# Small_robot_PCB_schematic.net
KiCad netlist of a schematic drawn in EAGLE
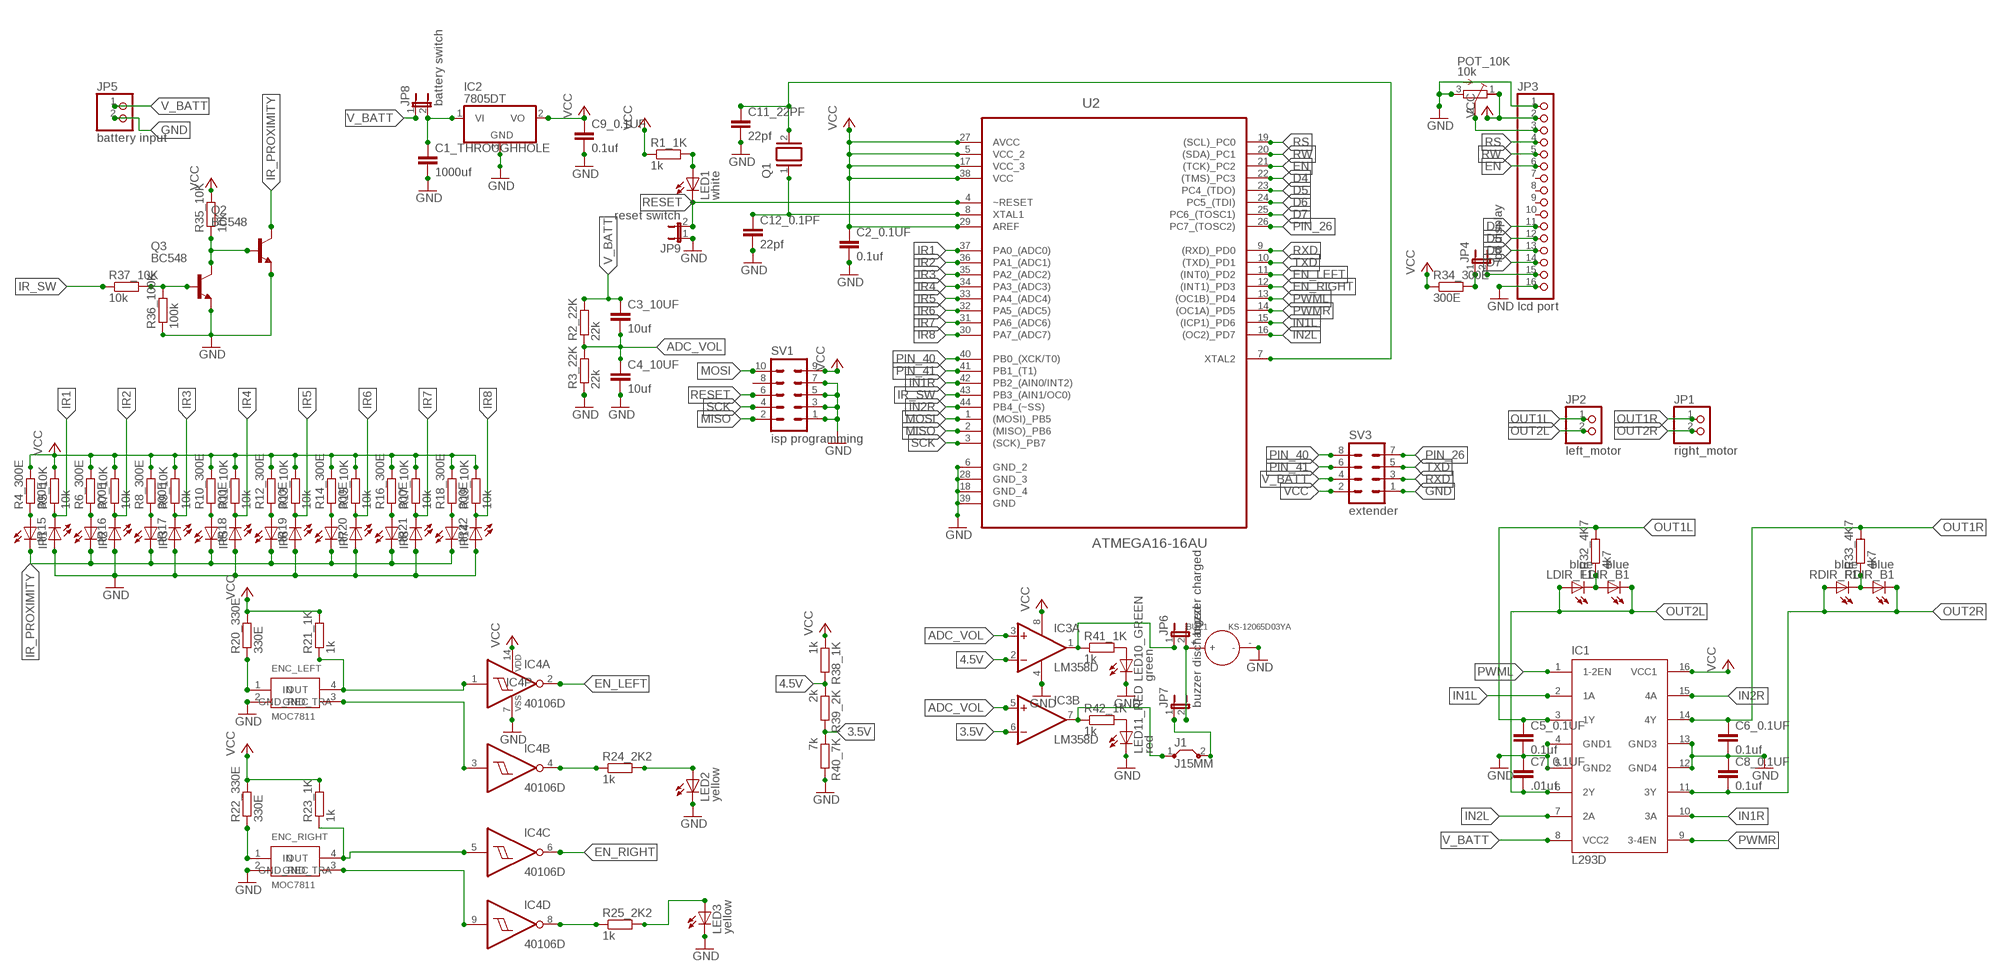
[diagram p0: schematic, sheet 1]

(export (version "E")
  (design (tool "Eeschema 10.0.6"))
  (components
    (comp (ref "BUZ1")
      (value "KS-12065D03YA")
      (footprint "eagle-import:BZ2-7.6-D12.0XH6.5MM")
      (libsource (lib "eagle-import") (part "DIP-BUZZER-3V(KS-12065D03YA)"))
    )
    (comp (ref "C1_THROUGHHOLE")
      (value "1000uf")
      (footprint "eagle-import:C050-045X075")
      (libsource (lib "eagle-import") (part "resistor_C-EU050-045X075"))
    )
    (comp (ref "C2_0.1UF")
      (value "0.1uf")
      (footprint "eagle-import:C1206")
      (libsource (lib "eagle-import") (part "resistor_C-EUC1206"))
    )
    (comp (ref "C3_10UF")
      (value "10uf")
      (footprint "eagle-import:C1206")
      (libsource (lib "eagle-import") (part "C-EUC1206"))
    )
    (comp (ref "C4_10UF")
      (value "10uf")
      (footprint "eagle-import:C1206")
      (libsource (lib "eagle-import") (part "C-EUC1206"))
    )
    (comp (ref "C5_0.1UF")
      (value "0.1uf")
      (footprint "eagle-import:C1206")
      (libsource (lib "eagle-import") (part "C-EUC1206"))
    )
    (comp (ref "C6_0.1UF")
      (value "0.1uf")
      (footprint "eagle-import:C1206")
      (libsource (lib "eagle-import") (part "C-EUC1206"))
    )
    (comp (ref "C7_0.1UF")
      (value ".01uf")
      (footprint "eagle-import:C1206")
      (libsource (lib "eagle-import") (part "C-EUC1206"))
    )
    (comp (ref "C8_0.1UF")
      (value "0.1uf")
      (footprint "eagle-import:C1206")
      (libsource (lib "eagle-import") (part "C-EUC1206"))
    )
    (comp (ref "C9_0.1UF")
      (value "0.1uf")
      (footprint "eagle-import:C1206")
      (libsource (lib "eagle-import") (part "resistor_C-EUC1206"))
    )
    (comp (ref "C11_22PF")
      (value "22pf")
      (footprint "eagle-import:C1206")
      (libsource (lib "eagle-import") (part "resistor_C-EUC1206"))
    )
    (comp (ref "C12_0.1PF")
      (value "22pf")
      (footprint "eagle-import:C1206")
      (libsource (lib "eagle-import") (part "resistor_C-EUC1206"))
    )
    (comp (ref "ENC_LEFT")
      (value "MOC7811")
      (footprint "eagle-import:THROUGH_HOLE_NORMAL")
      (libsource (lib "eagle-import") (part "MOC7811"))
    )
    (comp (ref "ENC_RIGHT")
      (value "MOC7811")
      (footprint "eagle-import:THROUGH_HOLE_NORMAL")
      (libsource (lib "eagle-import") (part "MOC7811"))
    )
    (comp (ref "IC1")
      (value "L293D")
      (footprint "eagle-import:DIL16")
      (libsource (lib "eagle-import") (part "L293D"))
    )
    (comp (ref "IC2")
      (value "7805DT")
      (footprint "eagle-import:TO252")
      (libsource (lib "eagle-import") (part "78DT05"))
    )
    (comp (ref "IC3")
      (value "LM358D")
      (footprint "eagle-import:SO08")
      (libsource (lib "eagle-import") (part "LM358D"))
    )
    (comp (ref "IC4")
      (value "40106D")
      (footprint "eagle-import:SO14")
      (libsource (lib "eagle-import") (part "40106D"))
    )
    (comp (ref "IR1")
      (value "LED5MM")
      (footprint "eagle-import:LED5MM")
      (libsource (lib "eagle-import") (part "LED5MM"))
    )
    (comp (ref "IR2")
      (value "LED5MM")
      (footprint "eagle-import:LED5MM")
      (libsource (lib "eagle-import") (part "LED5MM"))
    )
    (comp (ref "IR3")
      (value "LED5MM")
      (footprint "eagle-import:LED5MM")
      (libsource (lib "eagle-import") (part "LED5MM"))
    )
    (comp (ref "IR5")
      (value "LED5MM")
      (footprint "eagle-import:LED5MM")
      (libsource (lib "eagle-import") (part "LED5MM"))
    )
    (comp (ref "IR6")
      (value "LED5MM")
      (footprint "eagle-import:LED5MM")
      (libsource (lib "eagle-import") (part "LED5MM"))
    )
    (comp (ref "IR7")
      (value "LED5MM")
      (footprint "eagle-import:LED5MM")
      (libsource (lib "eagle-import") (part "LED5MM"))
    )
    (comp (ref "IR8")
      (value "LED5MM")
      (footprint "eagle-import:LED5MM")
      (libsource (lib "eagle-import") (part "LED5MM"))
    )
    (comp (ref "IR14")
      (value "LED5MM")
      (footprint "eagle-import:LED5MM")
      (libsource (lib "eagle-import") (part "LED5MM"))
    )
    (comp (ref "IR15")
      (value "LED5MM")
      (footprint "eagle-import:LED5MM")
      (libsource (lib "eagle-import") (part "LED5MM"))
    )
    (comp (ref "IR16")
      (value "LED5MM")
      (footprint "eagle-import:LED5MM")
      (libsource (lib "eagle-import") (part "LED5MM"))
    )
    (comp (ref "IR17")
      (value "LED5MM")
      (footprint "eagle-import:LED5MM")
      (libsource (lib "eagle-import") (part "LED5MM"))
    )
    (comp (ref "IR18")
      (value "LED5MM")
      (footprint "eagle-import:LED5MM")
      (libsource (lib "eagle-import") (part "LED5MM"))
    )
    (comp (ref "IR19")
      (value "LED5MM")
      (footprint "eagle-import:LED5MM")
      (libsource (lib "eagle-import") (part "LED5MM"))
    )
    (comp (ref "IR20")
      (value "LED5MM")
      (footprint "eagle-import:LED5MM")
      (libsource (lib "eagle-import") (part "LED5MM"))
    )
    (comp (ref "IR21")
      (value "LED5MM")
      (footprint "eagle-import:LED5MM")
      (libsource (lib "eagle-import") (part "LED5MM"))
    )
    (comp (ref "IR22")
      (value "LED5MM")
      (footprint "eagle-import:LED5MM")
      (libsource (lib "eagle-import") (part "LED5MM"))
    )
    (comp (ref "J1")
      (value "J15MM")
      (footprint "eagle-import:15")
      (libsource (lib "eagle-import") (part "J15MM"))
    )
    (comp (ref "JP1")
      (value "right_motor")
      (footprint "eagle-import:1X02")
      (libsource (lib "eagle-import") (part "PINHD-1X2"))
    )
    (comp (ref "JP2")
      (value "left_motor")
      (footprint "eagle-import:1X02")
      (libsource (lib "eagle-import") (part "PINHD-1X2"))
    )
    (comp (ref "JP3")
      (value "lcd port")
      (footprint "eagle-import:1X16")
      (libsource (lib "eagle-import") (part "PINHD-1X16"))
    )
    (comp (ref "JP4")
      (value "lcd display")
      (footprint "eagle-import:JP1")
      (libsource (lib "eagle-import") (part "JP1E"))
    )
    (comp (ref "JP5")
      (value "battery input")
      (footprint "eagle-import:1X02")
      (libsource (lib "eagle-import") (part "PINHD-1X2"))
    )
    (comp (ref "JP6")
      (value "buzzer charged")
      (footprint "eagle-import:JP1")
      (libsource (lib "eagle-import") (part "JP1E"))
    )
    (comp (ref "JP7")
      (value "buzzer discharged")
      (footprint "eagle-import:JP1")
      (libsource (lib "eagle-import") (part "JP1E"))
    )
    (comp (ref "JP8")
      (value "battery switch")
      (footprint "eagle-import:JP1")
      (libsource (lib "eagle-import") (part "JP1E"))
    )
    (comp (ref "JP9")
      (value "reset switch")
      (footprint "eagle-import:JP1")
      (libsource (lib "eagle-import") (part "JP1E"))
    )
    (comp (ref "LDIR_B1")
      (value "blue")
      (footprint "eagle-import:CHIPLED_1206")
      (libsource (lib "eagle-import") (part "LEDCHIPLED_1206"))
    )
    (comp (ref "LDIR_F1")
      (value "blue")
      (footprint "eagle-import:CHIPLED_1206")
      (libsource (lib "eagle-import") (part "LEDCHIPLED_1206"))
    )
    (comp (ref "LED1")
      (value "white")
      (footprint "eagle-import:CHIPLED_1206")
      (libsource (lib "eagle-import") (part "LEDCHIPLED_1206"))
    )
    (comp (ref "LED2")
      (value "yellow")
      (footprint "eagle-import:CHIPLED_1206")
      (libsource (lib "eagle-import") (part "LEDCHIPLED_1206"))
    )
    (comp (ref "LED3")
      (value "yellow")
      (footprint "eagle-import:CHIPLED_1206")
      (libsource (lib "eagle-import") (part "LEDCHIPLED_1206"))
    )
    (comp (ref "LED10_GREEN")
      (value "green")
      (footprint "eagle-import:CHIPLED_1206")
      (libsource (lib "eagle-import") (part "LEDCHIPLED_1206"))
    )
    (comp (ref "LED11_RED")
      (value "red")
      (footprint "eagle-import:CHIPLED_1206")
      (libsource (lib "eagle-import") (part "LEDCHIPLED_1206"))
    )
    (comp (ref "POT_10K")
      (value "10k")
      (footprint "eagle-import:RTRIMT93YA")
      (libsource (lib "eagle-import") (part "R-TRIMMT93YA"))
    )
    (comp (ref "Q1")
      (value "XTAL")
      (footprint "eagle-import:Q")
      (libsource (lib "eagle-import") (part "XTAL"))
    )
    (comp (ref "Q2")
      (value "BC548")
      (footprint "eagle-import:TO92-EBC")
      (libsource (lib "eagle-import") (part "BC548"))
    )
    (comp (ref "Q3")
      (value "BC548")
      (footprint "eagle-import:TO92-EBC")
      (libsource (lib "eagle-import") (part "BC548"))
    )
    (comp (ref "R1_1K")
      (value "1k")
      (footprint "eagle-import:R1206")
      (libsource (lib "eagle-import") (part "R-EU_R1206"))
    )
    (comp (ref "R2_22K")
      (value "22k")
      (footprint "eagle-import:R1206")
      (libsource (lib "eagle-import") (part "R-EU_R1206"))
    )
    (comp (ref "R3_22K")
      (value "22k")
      (footprint "eagle-import:R1206")
      (libsource (lib "eagle-import") (part "R-EU_R1206"))
    )
    (comp (ref "R4_300E")
      (value "300E")
      (footprint "eagle-import:R1206")
      (libsource (lib "eagle-import") (part "R-EU_R1206"))
    )
    (comp (ref "R5_10K")
      (value "10k")
      (footprint "eagle-import:R1206")
      (libsource (lib "eagle-import") (part "R-EU_R1206"))
    )
    (comp (ref "R6_300E")
      (value "300E")
      (footprint "eagle-import:R1206")
      (libsource (lib "eagle-import") (part "R-EU_R1206"))
    )
    (comp (ref "R7_10K")
      (value "10k")
      (footprint "eagle-import:R1206")
      (libsource (lib "eagle-import") (part "R-EU_R1206"))
    )
    (comp (ref "R8_300E")
      (value "300E")
      (footprint "eagle-import:R1206")
      (libsource (lib "eagle-import") (part "R-EU_R1206"))
    )
    (comp (ref "R9_10K")
      (value "10k")
      (footprint "eagle-import:R1206")
      (libsource (lib "eagle-import") (part "R-EU_R1206"))
    )
    (comp (ref "R10_300E")
      (value "300E")
      (footprint "eagle-import:R1206")
      (libsource (lib "eagle-import") (part "R-EU_R1206"))
    )
    (comp (ref "R11_10K")
      (value "10k")
      (footprint "eagle-import:R1206")
      (libsource (lib "eagle-import") (part "R-EU_R1206"))
    )
    (comp (ref "R12_300E")
      (value "300E")
      (footprint "eagle-import:R1206")
      (libsource (lib "eagle-import") (part "R-EU_R1206"))
    )
    (comp (ref "R13_10K")
      (value "10k")
      (footprint "eagle-import:R1206")
      (libsource (lib "eagle-import") (part "R-EU_R1206"))
    )
    (comp (ref "R14_300E")
      (value "300E")
      (footprint "eagle-import:R1206")
      (libsource (lib "eagle-import") (part "R-EU_R1206"))
    )
    (comp (ref "R15_10K")
      (value "10k")
      (footprint "eagle-import:R1206")
      (libsource (lib "eagle-import") (part "R-EU_R1206"))
    )
    (comp (ref "R16_300E")
      (value "300E")
      (footprint "eagle-import:R1206")
      (libsource (lib "eagle-import") (part "R-EU_R1206"))
    )
    (comp (ref "R17_10K")
      (value "10k")
      (footprint "eagle-import:R1206")
      (libsource (lib "eagle-import") (part "R-EU_R1206"))
    )
    (comp (ref "R18_300E")
      (value "300E")
      (footprint "eagle-import:R1206")
      (libsource (lib "eagle-import") (part "R-EU_R1206"))
    )
    (comp (ref "R19_10K")
      (value "10k")
      (footprint "eagle-import:R1206")
      (libsource (lib "eagle-import") (part "R-EU_R1206"))
    )
    (comp (ref "R20_330E")
      (value "330E")
      (footprint "eagle-import:R1206")
      (libsource (lib "eagle-import") (part "R-EU_R1206"))
    )
    (comp (ref "R21_1K")
      (value "1k")
      (footprint "eagle-import:R1206")
      (libsource (lib "eagle-import") (part "R-EU_R1206"))
    )
    (comp (ref "R22_330E")
      (value "330E")
      (footprint "eagle-import:R1206")
      (libsource (lib "eagle-import") (part "R-EU_R1206"))
    )
    (comp (ref "R23_1K")
      (value "1k")
      (footprint "eagle-import:R1206")
      (libsource (lib "eagle-import") (part "R-EU_R1206"))
    )
    (comp (ref "R24_2K2")
      (value "1k")
      (footprint "eagle-import:R1206")
      (libsource (lib "eagle-import") (part "R-EU_R1206"))
    )
    (comp (ref "R25_2K2")
      (value "1k")
      (footprint "eagle-import:R1206")
      (libsource (lib "eagle-import") (part "R-EU_R1206"))
    )
    (comp (ref "R32_4K7")
      (value "4k7")
      (footprint "eagle-import:R1206")
      (libsource (lib "eagle-import") (part "R-EU_R1206"))
    )
    (comp (ref "R33_4K7")
      (value "4k7")
      (footprint "eagle-import:R1206")
      (libsource (lib "eagle-import") (part "R-EU_R1206"))
    )
    (comp (ref "R34_300E")
      (value "300E")
      (footprint "eagle-import:R1206")
      (libsource (lib "eagle-import") (part "R-EU_R1206"))
    )
    (comp (ref "R35_10K")
      (value "10k")
      (footprint "eagle-import:R1206")
      (libsource (lib "eagle-import") (part "R-EU_R1206"))
    )
    (comp (ref "R36_100K")
      (value "100k")
      (footprint "eagle-import:R1206")
      (libsource (lib "eagle-import") (part "R-EU_R1206"))
    )
    (comp (ref "R37_10K")
      (value "10k")
      (footprint "eagle-import:R1206")
      (libsource (lib "eagle-import") (part "R-EU_R1206"))
    )
    (comp (ref "R38_1K")
      (value "1k")
      (footprint "eagle-import:R1206")
      (libsource (lib "eagle-import") (part "R-EU_R1206"))
    )
    (comp (ref "R39_2K")
      (value "2k")
      (footprint "eagle-import:R1206")
      (libsource (lib "eagle-import") (part "R-EU_R1206"))
    )
    (comp (ref "R40_7K")
      (value "7k")
      (footprint "eagle-import:R1206")
      (libsource (lib "eagle-import") (part "R-EU_R1206"))
    )
    (comp (ref "R41_1K")
      (value "1k")
      (footprint "eagle-import:R1206")
      (libsource (lib "eagle-import") (part "R-EU_R1206"))
    )
    (comp (ref "R42_1K")
      (value "1k")
      (footprint "eagle-import:R1206")
      (libsource (lib "eagle-import") (part "R-EU_R1206"))
    )
    (comp (ref "RDIR_B1")
      (value "blue")
      (footprint "eagle-import:CHIPLED_1206")
      (libsource (lib "eagle-import") (part "LEDCHIPLED_1206"))
    )
    (comp (ref "RDIR_F1")
      (value "blue")
      (footprint "eagle-import:CHIPLED_1206")
      (libsource (lib "eagle-import") (part "LEDCHIPLED_1206"))
    )
    (comp (ref "SV1")
      (value "isp programming")
      (footprint "eagle-import:MA05-2")
      (libsource (lib "eagle-import") (part "MA05-2"))
    )
    (comp (ref "SV3")
      (value "extender")
      (footprint "eagle-import:MA04-2")
      (libsource (lib "eagle-import") (part "MA04-2"))
    )
    (comp (ref "U2")
      (value "ATMEGA16-16AU")
      (footprint "eagle-import:QFP80P1200X1200X120-44N")
      (libsource (lib "eagle-import") (part "ATMEGA16-16AU"))
    )
  )
  (nets
    (net (code "1") (name "3.5V") (class "Default")
      (node (ref "IC3") (pin "6") (pinfunction "-IN_6") (pintype "input"))
      (node (ref "R39_2K") (pin "2") (pinfunction "2_2") (pintype "passive"))
      (node (ref "R40_7K") (pin "1") (pinfunction "1_1") (pintype "passive"))
    )
    (net (code "2") (name "4.5V") (class "Default")
      (node (ref "IC3") (pin "2") (pinfunction "-IN_2") (pintype "input"))
      (node (ref "R38_1K") (pin "2") (pinfunction "2_2") (pintype "passive"))
      (node (ref "R39_2K") (pin "1") (pinfunction "1_1") (pintype "passive"))
    )
    (net (code "3") (name "ADC_VOL") (class "Default")
      (node (ref "C3_10UF") (pin "2") (pinfunction "2_2") (pintype "passive"))
      (node (ref "C4_10UF") (pin "1") (pinfunction "1_1") (pintype "passive"))
      (node (ref "IC3") (pin "3") (pinfunction "+IN_3") (pintype "input"))
      (node (ref "IC3") (pin "5") (pinfunction "+IN_5") (pintype "input"))
      (node (ref "R2_22K") (pin "1") (pinfunction "1_1") (pintype "passive"))
      (node (ref "R3_22K") (pin "2") (pinfunction "2_2") (pintype "passive"))
    )
    (net (code "4") (name "D4") (class "Default")
      (node (ref "JP3") (pin "11") (pinfunction "11_11") (pintype "passive"))
      (node (ref "U2") (pin "22") (pinfunction "(TMS)_PC3_22") (pintype "bidirectional"))
    )
    (net (code "5") (name "D5") (class "Default")
      (node (ref "JP3") (pin "12") (pinfunction "12_12") (pintype "passive"))
      (node (ref "U2") (pin "23") (pinfunction "PC4_(TDO)_23") (pintype "bidirectional"))
    )
    (net (code "6") (name "D6") (class "Default")
      (node (ref "JP3") (pin "13") (pinfunction "13_13") (pintype "passive"))
      (node (ref "U2") (pin "24") (pinfunction "PC5_(TDI)_24") (pintype "bidirectional"))
    )
    (net (code "7") (name "D7") (class "Default")
      (node (ref "JP3") (pin "14") (pinfunction "14_14") (pintype "passive"))
      (node (ref "U2") (pin "25") (pinfunction "PC6_(TOSC1)_25") (pintype "bidirectional"))
    )
    (net (code "8") (name "EN") (class "Default")
      (node (ref "JP3") (pin "6") (pinfunction "6_6") (pintype "passive"))
      (node (ref "U2") (pin "21") (pinfunction "(TCK)_PC2_21") (pintype "bidirectional"))
    )
    (net (code "9") (name "EN_LEFT") (class "Default")
      (node (ref "IC4") (pin "2") (pinfunction "O_2") (pintype "output"))
      (node (ref "U2") (pin "11") (pinfunction "(INT0)_PD2_11") (pintype "bidirectional"))
    )
    (net (code "10") (name "EN_RIGHT") (class "Default")
      (node (ref "IC4") (pin "6") (pinfunction "O_6") (pintype "output"))
      (node (ref "U2") (pin "12") (pinfunction "(INT1)_PD3_12") (pintype "bidirectional"))
    )
    (net (code "11") (name "GND") (class "Default")
      (node (ref "BUZ1") (pin "-") (pinfunction "-_-") (pintype "bidirectional"))
      (node (ref "C11_22PF") (pin "2") (pinfunction "2_2") (pintype "passive"))
      (node (ref "C12_0.1PF") (pin "2") (pinfunction "2_2") (pintype "passive"))
      (node (ref "C1_THROUGHHOLE") (pin "2") (pinfunction "2_2") (pintype "passive"))
      (node (ref "C2_0.1UF") (pin "2") (pinfunction "2_2") (pintype "passive"))
      (node (ref "C4_10UF") (pin "2") (pinfunction "2_2") (pintype "passive"))
      (node (ref "C5_0.1UF") (pin "2") (pinfunction "2_2") (pintype "passive"))
      (node (ref "C6_0.1UF") (pin "2") (pinfunction "2_2") (pintype "passive"))
      (node (ref "C7_0.1UF") (pin "1") (pinfunction "1_1") (pintype "passive"))
      (node (ref "C8_0.1UF") (pin "1") (pinfunction "1_1") (pintype "passive"))
      (node (ref "C9_0.1UF") (pin "2") (pinfunction "2_2") (pintype "passive"))
      (node (ref "ENC_LEFT") (pin "2") (pinfunction "GND_TRA_2") (pintype "bidirectional"))
      (node (ref "ENC_RIGHT") (pin "2") (pinfunction "GND_TRA_2") (pintype "bidirectional"))
      (node (ref "IC1") (pin "12") (pinfunction "GND4_12") (pintype "power_in"))
      (node (ref "IC1") (pin "13") (pinfunction "GND3_13") (pintype "power_in"))
      (node (ref "IC1") (pin "4") (pinfunction "GND1_4") (pintype "power_in"))
      (node (ref "IC1") (pin "5") (pinfunction "GND2_5") (pintype "power_in"))
      (node (ref "IC2") (pin "3") (pinfunction "GND_3") (pintype "passive"))
      (node (ref "IC3") (pin "4") (pinfunction "V-_4") (pintype "power_in"))
      (node (ref "IC4") (pin "7") (pinfunction "VSS_7") (pintype "power_in"))
      (node (ref "IR15") (pin "A") (pinfunction "A_A") (pintype "passive"))
      (node (ref "IR16") (pin "A") (pinfunction "A_A") (pintype "passive"))
      (node (ref "IR17") (pin "A") (pinfunction "A_A") (pintype "passive"))
      (node (ref "IR18") (pin "A") (pinfunction "A_A") (pintype "passive"))
      (node (ref "IR19") (pin "A") (pinfunction "A_A") (pintype "passive"))
      (node (ref "IR20") (pin "A") (pinfunction "A_A") (pintype "passive"))
      (node (ref "IR21") (pin "A") (pinfunction "A_A") (pintype "passive"))
      (node (ref "IR22") (pin "A") (pinfunction "A_A") (pintype "passive"))
      (node (ref "JP3") (pin "1") (pinfunction "1_1") (pintype "passive"))
      (node (ref "JP3") (pin "16") (pinfunction "16_16") (pintype "passive"))
      (node (ref "JP5") (pin "2") (pinfunction "2_2") (pintype "passive"))
      (node (ref "JP9") (pin "1") (pinfunction "1_1") (pintype "passive"))
      (node (ref "LED10_GREEN") (pin "C") (pinfunction "C_C") (pintype "passive"))
      (node (ref "LED11_RED") (pin "C") (pinfunction "C_C") (pintype "passive"))
      (node (ref "LED2") (pin "C") (pinfunction "C_C") (pintype "passive"))
      (node (ref "LED3") (pin "C") (pinfunction "C_C") (pintype "passive"))
      (node (ref "POT_10K") (pin "3") (pinfunction "A_3") (pintype "passive"))
      (node (ref "Q2") (pin "E") (pinfunction "E_E") (pintype "passive"))
      (node (ref "Q3") (pin "E") (pinfunction "E_E") (pintype "passive"))
      (node (ref "R36_100K") (pin "1") (pinfunction "1_1") (pintype "passive"))
      (node (ref "R3_22K") (pin "1") (pinfunction "1_1") (pintype "passive"))
      (node (ref "R40_7K") (pin "2") (pinfunction "2_2") (pintype "passive"))
      (node (ref "SV1") (pin "1") (pinfunction "1_1") (pintype "passive"))
      (node (ref "SV1") (pin "3") (pinfunction "3_3") (pintype "passive"))
      (node (ref "SV1") (pin "5") (pinfunction "5_5") (pintype "passive"))
      (node (ref "SV1") (pin "7") (pinfunction "7_7") (pintype "passive"))
      (node (ref "SV3") (pin "1") (pinfunction "1_1") (pintype "passive"))
      (node (ref "U2") (pin "18") (pinfunction "GND_4_18") (pintype "passive"))
      (node (ref "U2") (pin "28") (pinfunction "GND_3_28") (pintype "passive"))
      (node (ref "U2") (pin "39") (pinfunction "GND_39") (pintype "passive"))
      (node (ref "U2") (pin "6") (pinfunction "GND_2_6") (pintype "passive"))
    )
    (net (code "12") (name "IN1L") (class "Default")
      (node (ref "IC1") (pin "2") (pinfunction "1A_2") (pintype "input"))
      (node (ref "U2") (pin "15") (pinfunction "(ICP1)_PD6_15") (pintype "bidirectional"))
    )
    (net (code "13") (name "IN1R") (class "Default")
      (node (ref "IC1") (pin "10") (pinfunction "3A_10") (pintype "input"))
      (node (ref "U2") (pin "42") (pinfunction "PB2_(AIN0/INT2)_42") (pintype "bidirectional"))
    )
    (net (code "14") (name "IN2L") (class "Default")
      (node (ref "IC1") (pin "7") (pinfunction "2A_7") (pintype "input"))
      (node (ref "U2") (pin "16") (pinfunction "(OC2)_PD7_16") (pintype "bidirectional"))
    )
    (net (code "15") (name "IN2R") (class "Default")
      (node (ref "IC1") (pin "15") (pinfunction "4A_15") (pintype "input"))
      (node (ref "U2") (pin "44") (pinfunction "PB4_(~{SS})_44") (pintype "bidirectional"))
    )
    (net (code "16") (name "IR1") (class "Default")
      (node (ref "IR15") (pin "K") (pinfunction "C_K") (pintype "passive"))
      (node (ref "R5_10K") (pin "1") (pinfunction "1_1") (pintype "passive"))
      (node (ref "U2") (pin "37") (pinfunction "PA0_(ADC0)_37") (pintype "bidirectional"))
    )
    (net (code "17") (name "IR2") (class "Default")
      (node (ref "IR16") (pin "K") (pinfunction "C_K") (pintype "passive"))
      (node (ref "R7_10K") (pin "1") (pinfunction "1_1") (pintype "passive"))
      (node (ref "U2") (pin "36") (pinfunction "PA1_(ADC1)_36") (pintype "bidirectional"))
    )
    (net (code "18") (name "IR3") (class "Default")
      (node (ref "IR17") (pin "K") (pinfunction "C_K") (pintype "passive"))
      (node (ref "R9_10K") (pin "1") (pinfunction "1_1") (pintype "passive"))
      (node (ref "U2") (pin "35") (pinfunction "PA2_(ADC2)_35") (pintype "bidirectional"))
    )
    (net (code "19") (name "IR4") (class "Default")
      (node (ref "IR18") (pin "K") (pinfunction "C_K") (pintype "passive"))
      (node (ref "R11_10K") (pin "1") (pinfunction "1_1") (pintype "passive"))
      (node (ref "U2") (pin "34") (pinfunction "PA3_(ADC3)_34") (pintype "bidirectional"))
    )
    (net (code "20") (name "IR5") (class "Default")
      (node (ref "IR19") (pin "K") (pinfunction "C_K") (pintype "passive"))
      (node (ref "R13_10K") (pin "1") (pinfunction "1_1") (pintype "passive"))
      (node (ref "U2") (pin "33") (pinfunction "PA4_(ADC4)_33") (pintype "bidirectional"))
    )
    (net (code "21") (name "IR6") (class "Default")
      (node (ref "IR20") (pin "K") (pinfunction "C_K") (pintype "passive"))
      (node (ref "R15_10K") (pin "1") (pinfunction "1_1") (pintype "passive"))
      (node (ref "U2") (pin "32") (pinfunction "PA5_(ADC5)_32") (pintype "bidirectional"))
    )
    (net (code "22") (name "IR7") (class "Default")
      (node (ref "IR21") (pin "K") (pinfunction "C_K") (pintype "passive"))
      (node (ref "R17_10K") (pin "1") (pinfunction "1_1") (pintype "passive"))
      (node (ref "U2") (pin "31") (pinfunction "PA6_(ADC6)_31") (pintype "bidirectional"))
    )
    (net (code "23") (name "IR8") (class "Default")
      (node (ref "IR22") (pin "K") (pinfunction "C_K") (pintype "passive"))
      (node (ref "R19_10K") (pin "1") (pinfunction "1_1") (pintype "passive"))
      (node (ref "U2") (pin "30") (pinfunction "PA7_(ADC7)_30") (pintype "bidirectional"))
    )
    (net (code "24") (name "IR_PROXIMITY") (class "Default")
      (node (ref "IR1") (pin "K") (pinfunction "C_K") (pintype "passive"))
      (node (ref "IR14") (pin "K") (pinfunction "C_K") (pintype "passive"))
      (node (ref "IR2") (pin "K") (pinfunction "C_K") (pintype "passive"))
      (node (ref "IR3") (pin "K") (pinfunction "C_K") (pintype "passive"))
      (node (ref "IR5") (pin "K") (pinfunction "C_K") (pintype "passive"))
      (node (ref "IR6") (pin "K") (pinfunction "C_K") (pintype "passive"))
      (node (ref "IR7") (pin "K") (pinfunction "C_K") (pintype "passive"))
      (node (ref "IR8") (pin "K") (pinfunction "C_K") (pintype "passive"))
      (node (ref "Q2") (pin "C") (pinfunction "C_C") (pintype "passive"))
    )
    (net (code "25") (name "IR_SW") (class "Default")
      (node (ref "R37_10K") (pin "1") (pinfunction "1_1") (pintype "passive"))
      (node (ref "U2") (pin "43") (pinfunction "PB3_(AIN1/OC0)_43") (pintype "bidirectional"))
    )
    (net (code "26") (name "MISO") (class "Default")
      (node (ref "SV1") (pin "2") (pinfunction "2_2") (pintype "passive"))
      (node (ref "U2") (pin "2") (pinfunction "(MISO)_PB6_2") (pintype "bidirectional"))
    )
    (net (code "27") (name "MOSI") (class "Default")
      (node (ref "SV1") (pin "10") (pinfunction "10_10") (pintype "passive"))
      (node (ref "U2") (pin "1") (pinfunction "(MOSI)_PB5_1") (pintype "bidirectional"))
    )
    (net (code "28") (name "Net-(BUZ1-Pad+)") (class "Default")
      (node (ref "BUZ1") (pin "+") (pinfunction "+_+") (pintype "bidirectional"))
      (node (ref "JP6") (pin "2") (pinfunction "2_2") (pintype "passive"))
      (node (ref "JP7") (pin "2") (pinfunction "2_2") (pintype "passive"))
    )
    (net (code "29") (name "Net-(ENC_LEFT-GND_REC)") (class "Default")
      (node (ref "ENC_LEFT") (pin "3") (pinfunction "GND_REC_3") (pintype "bidirectional"))
      (node (ref "IC4") (pin "3") (pinfunction "I_3") (pintype "input"))
    )
    (net (code "30") (name "Net-(ENC_LEFT-IN)") (class "Default")
      (node (ref "ENC_LEFT") (pin "1") (pinfunction "IN_1") (pintype "bidirectional"))
      (node (ref "R20_330E") (pin "1") (pinfunction "1_1") (pintype "passive"))
    )
    (net (code "31") (name "Net-(ENC_LEFT-OUT)") (class "Default")
      (node (ref "ENC_LEFT") (pin "4") (pinfunction "OUT_4") (pintype "bidirectional"))
      (node (ref "IC4") (pin "1") (pinfunction "I_1") (pintype "input"))
      (node (ref "R21_1K") (pin "1") (pinfunction "1_1") (pintype "passive"))
    )
    (net (code "32") (name "Net-(ENC_RIGHT-GND_REC)") (class "Default")
      (node (ref "ENC_RIGHT") (pin "3") (pinfunction "GND_REC_3") (pintype "bidirectional"))
      (node (ref "IC4") (pin "9") (pinfunction "I_9") (pintype "input"))
    )
    (net (code "33") (name "Net-(ENC_RIGHT-IN)") (class "Default")
      (node (ref "ENC_RIGHT") (pin "1") (pinfunction "IN_1") (pintype "bidirectional"))
      (node (ref "R22_330E") (pin "1") (pinfunction "1_1") (pintype "passive"))
    )
    (net (code "34") (name "Net-(ENC_RIGHT-OUT)") (class "Default")
      (node (ref "ENC_RIGHT") (pin "4") (pinfunction "OUT_4") (pintype "bidirectional"))
      (node (ref "IC4") (pin "5") (pinfunction "I_5") (pintype "input"))
      (node (ref "R23_1K") (pin "1") (pinfunction "1_1") (pintype "passive"))
    )
    (net (code "35") (name "Net-(IC2-VI)") (class "Default")
      (node (ref "C1_THROUGHHOLE") (pin "1") (pinfunction "1_1") (pintype "passive"))
      (node (ref "IC2") (pin "1") (pinfunction "VI_1") (pintype "input"))
      (node (ref "JP8") (pin "2") (pinfunction "2_2") (pintype "passive"))
    )
    (net (code "36") (name "Net-(IC3A-OUT)") (class "Default")
      (node (ref "IC3") (pin "1") (pinfunction "OUT_1") (pintype "output"))
      (node (ref "JP6") (pin "1") (pinfunction "1_1") (pintype "passive"))
      (node (ref "R41_1K") (pin "1") (pinfunction "1_1") (pintype "passive"))
    )
    (net (code "37") (name "Net-(IC3B-OUT)") (class "Default")
      (node (ref "IC3") (pin "7") (pinfunction "OUT_7") (pintype "output"))
      (node (ref "J1") (pin "1") (pinfunction "1_1") (pintype "passive"))
      (node (ref "R42_1K") (pin "1") (pinfunction "1_1") (pintype "passive"))
    )
    (net (code "38") (name "Net-(IC4B-O)") (class "Default")
      (node (ref "IC4") (pin "4") (pinfunction "O_4") (pintype "output"))
      (node (ref "R24_2K2") (pin "1") (pinfunction "1_1") (pintype "passive"))
    )
    (net (code "39") (name "Net-(IC4D-O)") (class "Default")
      (node (ref "IC4") (pin "8") (pinfunction "O_8") (pintype "output"))
      (node (ref "R25_2K2") (pin "1") (pinfunction "1_1") (pintype "passive"))
    )
    (net (code "40") (name "Net-(IR1-PadA)") (class "Default")
      (node (ref "IR1") (pin "A") (pinfunction "A_A") (pintype "passive"))
      (node (ref "R4_300E") (pin "1") (pinfunction "1_1") (pintype "passive"))
    )
    (net (code "41") (name "Net-(IR2-PadA)") (class "Default")
      (node (ref "IR2") (pin "A") (pinfunction "A_A") (pintype "passive"))
      (node (ref "R6_300E") (pin "1") (pinfunction "1_1") (pintype "passive"))
    )
    (net (code "42") (name "Net-(IR3-PadA)") (class "Default")
      (node (ref "IR3") (pin "A") (pinfunction "A_A") (pintype "passive"))
      (node (ref "R8_300E") (pin "1") (pinfunction "1_1") (pintype "passive"))
    )
    (net (code "43") (name "Net-(IR5-PadA)") (class "Default")
      (node (ref "IR5") (pin "A") (pinfunction "A_A") (pintype "passive"))
      (node (ref "R10_300E") (pin "1") (pinfunction "1_1") (pintype "passive"))
    )
    (net (code "44") (name "Net-(IR6-PadA)") (class "Default")
      (node (ref "IR6") (pin "A") (pinfunction "A_A") (pintype "passive"))
      (node (ref "R12_300E") (pin "1") (pinfunction "1_1") (pintype "passive"))
    )
    (net (code "45") (name "Net-(IR7-PadA)") (class "Default")
      (node (ref "IR7") (pin "A") (pinfunction "A_A") (pintype "passive"))
      (node (ref "R14_300E") (pin "1") (pinfunction "1_1") (pintype "passive"))
    )
    (net (code "46") (name "Net-(IR8-PadA)") (class "Default")
      (node (ref "IR8") (pin "A") (pinfunction "A_A") (pintype "passive"))
      (node (ref "R16_300E") (pin "1") (pinfunction "1_1") (pintype "passive"))
    )
    (net (code "47") (name "Net-(IR14-PadA)") (class "Default")
      (node (ref "IR14") (pin "A") (pinfunction "A_A") (pintype "passive"))
      (node (ref "R18_300E") (pin "1") (pinfunction "1_1") (pintype "passive"))
    )
    (net (code "48") (name "Net-(J1-Pad2)") (class "Default")
      (node (ref "J1") (pin "2") (pinfunction "2_2") (pintype "passive"))
      (node (ref "JP7") (pin "1") (pinfunction "1_1") (pintype "passive"))
    )
    (net (code "49") (name "Net-(JP3-Pad15)") (class "Default")
      (node (ref "JP3") (pin "15") (pinfunction "15_15") (pintype "passive"))
      (node (ref "JP4") (pin "2") (pinfunction "2_2") (pintype "passive"))
    )
    (net (code "50") (name "Net-(JP4-Pad1)") (class "Default")
      (node (ref "JP4") (pin "1") (pinfunction "1_1") (pintype "passive"))
      (node (ref "R34_300E") (pin "2") (pinfunction "2_2") (pintype "passive"))
    )
    (net (code "51") (name "Net-(LDIR_B1-PadA)") (class "Default")
      (node (ref "LDIR_B1") (pin "A") (pinfunction "A_A") (pintype "passive"))
      (node (ref "LDIR_F1") (pin "C") (pinfunction "C_C") (pintype "passive"))
      (node (ref "R32_4K7") (pin "1") (pinfunction "1_1") (pintype "passive"))
    )
    (net (code "52") (name "Net-(LED1-PadA)") (class "Default")
      (node (ref "LED1") (pin "A") (pinfunction "A_A") (pintype "passive"))
      (node (ref "R1_1K") (pin "2") (pinfunction "2_2") (pintype "passive"))
    )
    (net (code "53") (name "Net-(LED2-PadA)") (class "Default")
      (node (ref "LED2") (pin "A") (pinfunction "A_A") (pintype "passive"))
      (node (ref "R24_2K2") (pin "2") (pinfunction "2_2") (pintype "passive"))
    )
    (net (code "54") (name "Net-(LED3-PadA)") (class "Default")
      (node (ref "LED3") (pin "A") (pinfunction "A_A") (pintype "passive"))
      (node (ref "R25_2K2") (pin "2") (pinfunction "2_2") (pintype "passive"))
    )
    (net (code "55") (name "Net-(LED10_GREEN-PadA)") (class "Default")
      (node (ref "LED10_GREEN") (pin "A") (pinfunction "A_A") (pintype "passive"))
      (node (ref "R41_1K") (pin "2") (pinfunction "2_2") (pintype "passive"))
    )
    (net (code "56") (name "Net-(LED11_RED-PadA)") (class "Default")
      (node (ref "LED11_RED") (pin "A") (pinfunction "A_A") (pintype "passive"))
      (node (ref "R42_1K") (pin "2") (pinfunction "2_2") (pintype "passive"))
    )
    (net (code "57") (name "Net-(POT_10K-S)") (class "Default")
      (node (ref "JP3") (pin "3") (pinfunction "3_3") (pintype "passive"))
      (node (ref "POT_10K") (pin "2") (pinfunction "S_2") (pintype "passive"))
    )
    (net (code "58") (name "Net-(Q2-PadB)") (class "Default")
      (node (ref "Q2") (pin "B") (pinfunction "B_B") (pintype "passive"))
      (node (ref "Q3") (pin "C") (pinfunction "C_C") (pintype "passive"))
      (node (ref "R35_10K") (pin "1") (pinfunction "1_1") (pintype "passive"))
    )
    (net (code "59") (name "Net-(Q3-PadB)") (class "Default")
      (node (ref "Q3") (pin "B") (pinfunction "B_B") (pintype "passive"))
      (node (ref "R36_100K") (pin "2") (pinfunction "2_2") (pintype "passive"))
      (node (ref "R37_10K") (pin "2") (pinfunction "2_2") (pintype "passive"))
    )
    (net (code "60") (name "Net-(R33_4K7-Pad1)") (class "Default")
      (node (ref "R33_4K7") (pin "1") (pinfunction "1_1") (pintype "passive"))
      (node (ref "RDIR_B1") (pin "A") (pinfunction "A_A") (pintype "passive"))
      (node (ref "RDIR_F1") (pin "C") (pinfunction "C_C") (pintype "passive"))
    )
    (net (code "61") (name "Net-(U2-XTAL1)") (class "Default")
      (node (ref "C12_0.1PF") (pin "1") (pinfunction "1_1") (pintype "passive"))
      (node (ref "Q1") (pin "1") (pinfunction "1_1") (pintype "passive"))
      (node (ref "U2") (pin "8") (pinfunction "XTAL1_8") (pintype "input"))
    )
    (net (code "62") (name "Net-(U2-XTAL2)") (class "Default")
      (node (ref "C11_22PF") (pin "1") (pinfunction "1_1") (pintype "passive"))
      (node (ref "Q1") (pin "2") (pinfunction "2_2") (pintype "passive"))
      (node (ref "U2") (pin "7") (pinfunction "XTAL2_7") (pintype "output"))
    )
    (net (code "63") (name "OUT1L") (class "Default")
      (node (ref "C5_0.1UF") (pin "1") (pinfunction "1_1") (pintype "passive"))
      (node (ref "IC1") (pin "3") (pinfunction "1Y_3") (pintype "output"))
      (node (ref "JP2") (pin "1") (pinfunction "1_1") (pintype "passive"))
      (node (ref "R32_4K7") (pin "2") (pinfunction "2_2") (pintype "passive"))
    )
    (net (code "64") (name "OUT1R") (class "Default")
      (node (ref "C6_0.1UF") (pin "1") (pinfunction "1_1") (pintype "passive"))
      (node (ref "IC1") (pin "14") (pinfunction "4Y_14") (pintype "output"))
      (node (ref "JP1") (pin "1") (pinfunction "1_1") (pintype "passive"))
      (node (ref "R33_4K7") (pin "2") (pinfunction "2_2") (pintype "passive"))
    )
    (net (code "65") (name "OUT2L") (class "Default")
      (node (ref "C7_0.1UF") (pin "2") (pinfunction "2_2") (pintype "passive"))
      (node (ref "IC1") (pin "6") (pinfunction "2Y_6") (pintype "output"))
      (node (ref "JP2") (pin "2") (pinfunction "2_2") (pintype "passive"))
      (node (ref "LDIR_B1") (pin "C") (pinfunction "C_C") (pintype "passive"))
      (node (ref "LDIR_F1") (pin "A") (pinfunction "A_A") (pintype "passive"))
    )
    (net (code "66") (name "OUT2R") (class "Default")
      (node (ref "C8_0.1UF") (pin "2") (pinfunction "2_2") (pintype "passive"))
      (node (ref "IC1") (pin "11") (pinfunction "3Y_11") (pintype "output"))
      (node (ref "JP1") (pin "2") (pinfunction "2_2") (pintype "passive"))
      (node (ref "RDIR_B1") (pin "C") (pinfunction "C_C") (pintype "passive"))
      (node (ref "RDIR_F1") (pin "A") (pinfunction "A_A") (pintype "passive"))
    )
    (net (code "67") (name "PIN_26") (class "Default")
      (node (ref "SV3") (pin "7") (pinfunction "7_7") (pintype "passive"))
      (node (ref "U2") (pin "26") (pinfunction "PC7_(TOSC2)_26") (pintype "bidirectional"))
    )
    (net (code "68") (name "PIN_40") (class "Default")
      (node (ref "SV3") (pin "8") (pinfunction "8_8") (pintype "passive"))
      (node (ref "U2") (pin "40") (pinfunction "PB0_(XCK/T0)_40") (pintype "bidirectional"))
    )
    (net (code "69") (name "PIN_41") (class "Default")
      (node (ref "SV3") (pin "6") (pinfunction "6_6") (pintype "passive"))
      (node (ref "U2") (pin "41") (pinfunction "PB1_(T1)_41") (pintype "bidirectional"))
    )
    (net (code "70") (name "PWML") (class "Default")
      (node (ref "IC1") (pin "1") (pinfunction "1-2EN_1") (pintype "input"))
      (node (ref "U2") (pin "13") (pinfunction "(OC1B)_PD4_13") (pintype "bidirectional"))
    )
    (net (code "71") (name "PWMR") (class "Default")
      (node (ref "IC1") (pin "9") (pinfunction "3-4EN_9") (pintype "input"))
      (node (ref "U2") (pin "14") (pinfunction "(OC1A)_PD5_14") (pintype "bidirectional"))
    )
    (net (code "72") (name "RESET") (class "Default")
      (node (ref "JP9") (pin "2") (pinfunction "2_2") (pintype "passive"))
      (node (ref "LED1") (pin "C") (pinfunction "C_C") (pintype "passive"))
      (node (ref "SV1") (pin "6") (pinfunction "6_6") (pintype "passive"))
      (node (ref "U2") (pin "4") (pinfunction "~{RESET}_4") (pintype "input"))
    )
    (net (code "73") (name "RS") (class "Default")
      (node (ref "JP3") (pin "4") (pinfunction "4_4") (pintype "passive"))
      (node (ref "U2") (pin "19") (pinfunction "(SCL)_PC0_19") (pintype "bidirectional"))
    )
    (net (code "74") (name "RW") (class "Default")
      (node (ref "JP3") (pin "5") (pinfunction "5_5") (pintype "passive"))
      (node (ref "U2") (pin "20") (pinfunction "(SDA)_PC1_20") (pintype "bidirectional"))
    )
    (net (code "75") (name "RXD") (class "Default")
      (node (ref "SV3") (pin "3") (pinfunction "3_3") (pintype "passive"))
      (node (ref "U2") (pin "9") (pinfunction "(RXD)_PD0_9") (pintype "bidirectional"))
    )
    (net (code "76") (name "SCK") (class "Default")
      (node (ref "SV1") (pin "4") (pinfunction "4_4") (pintype "passive"))
      (node (ref "U2") (pin "3") (pinfunction "(SCK)_PB7_3") (pintype "bidirectional"))
    )
    (net (code "77") (name "TXD") (class "Default")
      (node (ref "SV3") (pin "5") (pinfunction "5_5") (pintype "passive"))
      (node (ref "U2") (pin "10") (pinfunction "(TXD)_PD1_10") (pintype "bidirectional"))
    )
    (net (code "78") (name "VCC") (class "Default")
      (node (ref "C2_0.1UF") (pin "1") (pinfunction "1_1") (pintype "passive"))
      (node (ref "C9_0.1UF") (pin "1") (pinfunction "1_1") (pintype "passive"))
      (node (ref "IC1") (pin "16") (pinfunction "VCC1_16") (pintype "power_in"))
      (node (ref "IC2") (pin "2") (pinfunction "VO_2") (pintype "passive"))
      (node (ref "IC3") (pin "8") (pinfunction "V+_8") (pintype "power_in"))
      (node (ref "IC4") (pin "14") (pinfunction "VDD_14") (pintype "power_in"))
      (node (ref "JP3") (pin "2") (pinfunction "2_2") (pintype "passive"))
      (node (ref "POT_10K") (pin "1") (pinfunction "E_1") (pintype "passive"))
      (node (ref "R10_300E") (pin "2") (pinfunction "2_2") (pintype "passive"))
      (node (ref "R11_10K") (pin "2") (pinfunction "2_2") (pintype "passive"))
      (node (ref "R12_300E") (pin "2") (pinfunction "2_2") (pintype "passive"))
      (node (ref "R13_10K") (pin "2") (pinfunction "2_2") (pintype "passive"))
      (node (ref "R14_300E") (pin "2") (pinfunction "2_2") (pintype "passive"))
      (node (ref "R15_10K") (pin "2") (pinfunction "2_2") (pintype "passive"))
      (node (ref "R16_300E") (pin "2") (pinfunction "2_2") (pintype "passive"))
      (node (ref "R17_10K") (pin "2") (pinfunction "2_2") (pintype "passive"))
      (node (ref "R18_300E") (pin "2") (pinfunction "2_2") (pintype "passive"))
      (node (ref "R19_10K") (pin "2") (pinfunction "2_2") (pintype "passive"))
      (node (ref "R1_1K") (pin "1") (pinfunction "1_1") (pintype "passive"))
      (node (ref "R20_330E") (pin "2") (pinfunction "2_2") (pintype "passive"))
      (node (ref "R21_1K") (pin "2") (pinfunction "2_2") (pintype "passive"))
      (node (ref "R22_330E") (pin "2") (pinfunction "2_2") (pintype "passive"))
      (node (ref "R23_1K") (pin "2") (pinfunction "2_2") (pintype "passive"))
      (node (ref "R34_300E") (pin "1") (pinfunction "1_1") (pintype "passive"))
      (node (ref "R35_10K") (pin "2") (pinfunction "2_2") (pintype "passive"))
      (node (ref "R38_1K") (pin "1") (pinfunction "1_1") (pintype "passive"))
      (node (ref "R4_300E") (pin "2") (pinfunction "2_2") (pintype "passive"))
      (node (ref "R5_10K") (pin "2") (pinfunction "2_2") (pintype "passive"))
      (node (ref "R6_300E") (pin "2") (pinfunction "2_2") (pintype "passive"))
      (node (ref "R7_10K") (pin "2") (pinfunction "2_2") (pintype "passive"))
      (node (ref "R8_300E") (pin "2") (pinfunction "2_2") (pintype "passive"))
      (node (ref "R9_10K") (pin "2") (pinfunction "2_2") (pintype "passive"))
      (node (ref "SV1") (pin "9") (pinfunction "9_9") (pintype "passive"))
      (node (ref "SV3") (pin "2") (pinfunction "2_2") (pintype "passive"))
      (node (ref "U2") (pin "17") (pinfunction "VCC_3_17") (pintype "power_in"))
      (node (ref "U2") (pin "27") (pinfunction "AVCC_27") (pintype "power_in"))
      (node (ref "U2") (pin "29") (pinfunction "AREF_29") (pintype "input"))
      (node (ref "U2") (pin "38") (pinfunction "VCC_38") (pintype "power_in"))
      (node (ref "U2") (pin "5") (pinfunction "VCC_2_5") (pintype "power_in"))
    )
    (net (code "79") (name "V_BATT") (class "Default")
      (node (ref "C3_10UF") (pin "1") (pinfunction "1_1") (pintype "passive"))
      (node (ref "IC1") (pin "8") (pinfunction "VCC2_8") (pintype "power_in"))
      (node (ref "JP5") (pin "1") (pinfunction "1_1") (pintype "passive"))
      (node (ref "JP8") (pin "1") (pinfunction "1_1") (pintype "passive"))
      (node (ref "R2_22K") (pin "2") (pinfunction "2_2") (pintype "passive"))
      (node (ref "SV3") (pin "4") (pinfunction "4_4") (pintype "passive"))
    )
    (net (code "80") (name "unconnected-(JP3-Pad7)") (class "Default")
      (node (ref "JP3") (pin "7") (pinfunction "7_7") (pintype "passive"))
    )
    (net (code "81") (name "unconnected-(JP3-Pad8)") (class "Default")
      (node (ref "JP3") (pin "8") (pinfunction "8_8") (pintype "passive"))
    )
    (net (code "82") (name "unconnected-(JP3-Pad9)") (class "Default")
      (node (ref "JP3") (pin "9") (pinfunction "9_9") (pintype "passive"))
    )
    (net (code "83") (name "unconnected-(JP3-Pad10)") (class "Default")
      (node (ref "JP3") (pin "10") (pinfunction "10_10") (pintype "passive"))
    )
    (net (code "84") (name "unconnected-(SV1-Pad8)") (class "Default")
      (node (ref "SV1") (pin "8") (pinfunction "8_8") (pintype "passive"))
    )
  )
)
